# SMD_cree_driver_led-mosfet0023-GoldPhoen.net
KiCad netlist of a schematic drawn in EAGLE
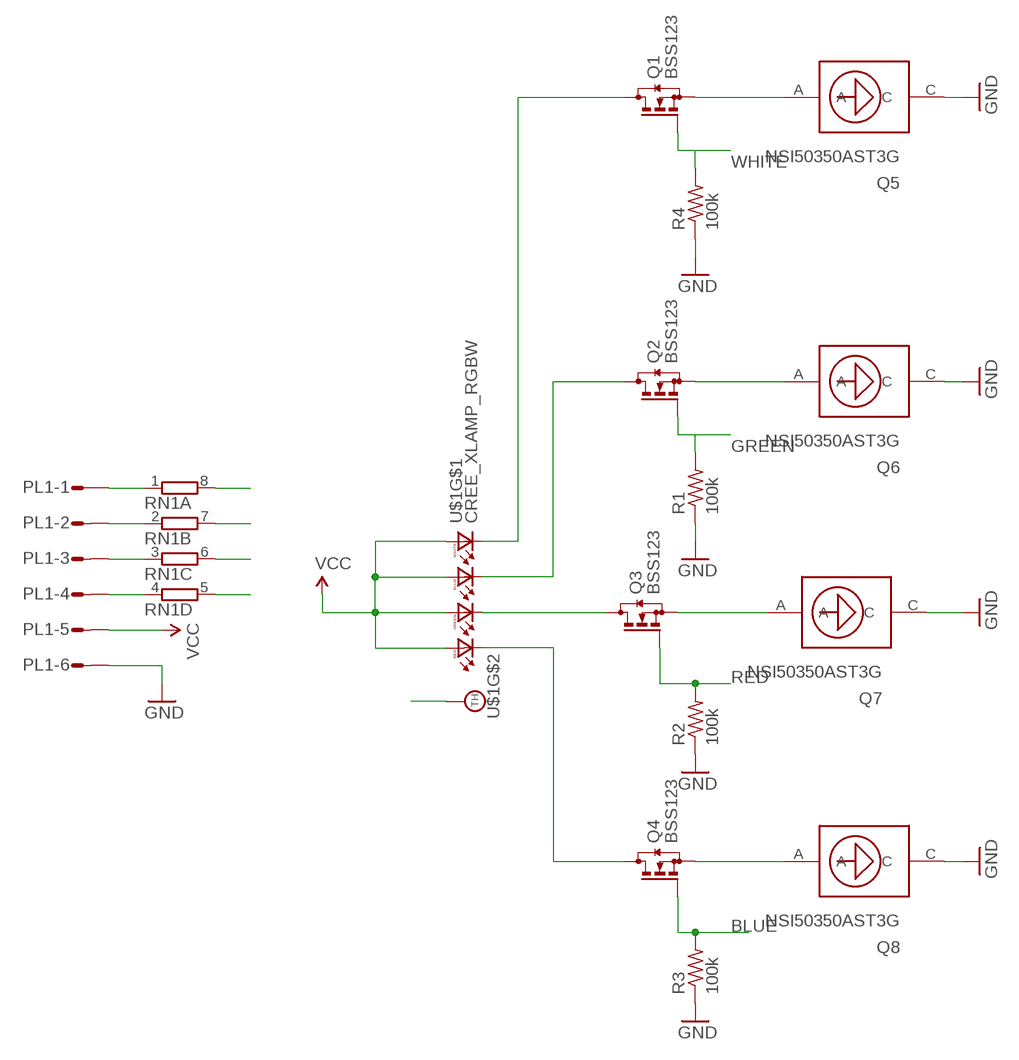
[diagram p0: schematic, sheet 1]

(export (version "E")
  (design (tool "Eeschema 10.0.6"))
  (components
    (comp (ref "PL1")
      (value "DF3-06R")
      (footprint "eagle-import:DF3R-06")
      (libsource (lib "eagle-import") (part "DF3-06R"))
    )
    (comp (ref "Q1")
      (value "BSS123")
      (footprint "eagle-import:SOT23")
      (libsource (lib "eagle-import") (part "BSS123"))
    )
    (comp (ref "Q2")
      (value "BSS123")
      (footprint "eagle-import:SOT23")
      (libsource (lib "eagle-import") (part "BSS123"))
    )
    (comp (ref "Q3")
      (value "BSS123")
      (footprint "eagle-import:SOT23")
      (libsource (lib "eagle-import") (part "BSS123"))
    )
    (comp (ref "Q4")
      (value "BSS123")
      (footprint "eagle-import:SOT23")
      (libsource (lib "eagle-import") (part "BSS123"))
    )
    (comp (ref "Q5")
      (value "NSI50350AST3G")
      (footprint "eagle-import:SMC-2")
      (libsource (lib "eagle-import") (part "NSI50350AST3G"))
    )
    (comp (ref "Q6")
      (value "NSI50350AST3G")
      (footprint "eagle-import:SMC-2")
      (libsource (lib "eagle-import") (part "NSI50350AST3G"))
    )
    (comp (ref "Q7")
      (value "NSI50350AST3G")
      (footprint "eagle-import:SMC-2")
      (libsource (lib "eagle-import") (part "NSI50350AST3G"))
    )
    (comp (ref "Q8")
      (value "NSI50350AST3G")
      (footprint "eagle-import:SMC-2")
      (libsource (lib "eagle-import") (part "NSI50350AST3G"))
    )
    (comp (ref "R1")
      (value "100k")
      (footprint "eagle-import:R0402")
      (libsource (lib "eagle-import") (part "R-US_R0402"))
    )
    (comp (ref "R2")
      (value "100k")
      (footprint "eagle-import:R0402")
      (libsource (lib "eagle-import") (part "R-US_R0402"))
    )
    (comp (ref "R3")
      (value "100k")
      (footprint "eagle-import:R0402")
      (libsource (lib "eagle-import") (part "R-US_R0402"))
    )
    (comp (ref "R4")
      (value "100k")
      (footprint "eagle-import:R0402")
      (libsource (lib "eagle-import") (part "R-US_R0402"))
    )
    (comp (ref "RN1")
      (value "4R-N0603-ARC")
      (footprint "eagle-import:0603-ARC")
      (libsource (lib "eagle-import") (part "4R-N0603-ARC"))
    )
    (comp (ref "U$1")
      (value "CREE_XLAMP_RGBW")
      (footprint "eagle-import:CREE_XLAMP_XML")
      (libsource (lib "eagle-import") (part "CREE_XLAMP_RGBW"))
    )
  )
  (nets
    (net (code "1") (name "/BLUE") (class "Default")
      (node (ref "Q4") (pin "1") (pinfunction "G_1") (pintype "passive"))
      (node (ref "R3") (pin "2") (pinfunction "2_2") (pintype "passive"))
      (node (ref "RN1") (pin "7") (pinfunction "2_7") (pintype "passive"))
    )
    (net (code "2") (name "/GREEN") (class "Default")
      (node (ref "Q2") (pin "1") (pinfunction "G_1") (pintype "passive"))
      (node (ref "R1") (pin "2") (pinfunction "2_2") (pintype "passive"))
      (node (ref "RN1") (pin "6") (pinfunction "2_6") (pintype "passive"))
    )
    (net (code "3") (name "/RED") (class "Default")
      (node (ref "Q3") (pin "1") (pinfunction "G_1") (pintype "passive"))
      (node (ref "R2") (pin "2") (pinfunction "2_2") (pintype "passive"))
      (node (ref "RN1") (pin "5") (pinfunction "2_5") (pintype "passive"))
    )
    (net (code "4") (name "/WHITE") (class "Default")
      (node (ref "Q1") (pin "1") (pinfunction "G_1") (pintype "passive"))
      (node (ref "R4") (pin "2") (pinfunction "2_2") (pintype "passive"))
      (node (ref "RN1") (pin "8") (pinfunction "2_8") (pintype "passive"))
    )
    (net (code "5") (name "GND") (class "Default")
      (node (ref "PL1") (pin "6") (pinfunction "S_6") (pintype "passive"))
      (node (ref "Q5") (pin "C") (pinfunction "C_C") (pintype "bidirectional"))
      (node (ref "Q6") (pin "C") (pinfunction "C_C") (pintype "bidirectional"))
      (node (ref "Q7") (pin "C") (pinfunction "C_C") (pintype "bidirectional"))
      (node (ref "Q8") (pin "C") (pinfunction "C_C") (pintype "bidirectional"))
      (node (ref "R1") (pin "1") (pinfunction "1_1") (pintype "passive"))
      (node (ref "R2") (pin "1") (pinfunction "1_1") (pintype "passive"))
      (node (ref "R3") (pin "1") (pinfunction "1_1") (pintype "passive"))
      (node (ref "R4") (pin "1") (pinfunction "1_1") (pintype "passive"))
    )
    (net (code "6") (name "Net-(PL1A-S)") (class "Default")
      (node (ref "PL1") (pin "1") (pinfunction "S_1") (pintype "passive"))
      (node (ref "RN1") (pin "1") (pinfunction "1_1") (pintype "passive"))
    )
    (net (code "7") (name "Net-(PL1B-S)") (class "Default")
      (node (ref "PL1") (pin "2") (pinfunction "S_2") (pintype "passive"))
      (node (ref "RN1") (pin "2") (pinfunction "1_2") (pintype "passive"))
    )
    (net (code "8") (name "Net-(PL1C-S)") (class "Default")
      (node (ref "PL1") (pin "3") (pinfunction "S_3") (pintype "passive"))
      (node (ref "RN1") (pin "3") (pinfunction "1_3") (pintype "passive"))
    )
    (net (code "9") (name "Net-(PL1D-S)") (class "Default")
      (node (ref "PL1") (pin "4") (pinfunction "S_4") (pintype "passive"))
      (node (ref "RN1") (pin "4") (pinfunction "1_4") (pintype "passive"))
    )
    (net (code "10") (name "Net-(Q1-D)") (class "Default")
      (node (ref "Q1") (pin "3") (pinfunction "D_3") (pintype "passive"))
      (node (ref "U$1") (pin "5") (pinfunction "WC_5") (pintype "passive"))
    )
    (net (code "11") (name "Net-(Q1-S)") (class "Default")
      (node (ref "Q1") (pin "2") (pinfunction "S_2") (pintype "passive"))
      (node (ref "Q5") (pin "A") (pinfunction "A_A") (pintype "bidirectional"))
    )
    (net (code "12") (name "Net-(Q2-D)") (class "Default")
      (node (ref "Q2") (pin "3") (pinfunction "D_3") (pintype "passive"))
      (node (ref "U$1") (pin "6") (pinfunction "BC_6") (pintype "passive"))
    )
    (net (code "13") (name "Net-(Q2-S)") (class "Default")
      (node (ref "Q2") (pin "2") (pinfunction "S_2") (pintype "passive"))
      (node (ref "Q6") (pin "A") (pinfunction "A_A") (pintype "bidirectional"))
    )
    (net (code "14") (name "Net-(Q3-D)") (class "Default")
      (node (ref "Q3") (pin "3") (pinfunction "D_3") (pintype "passive"))
      (node (ref "U$1") (pin "7") (pinfunction "GC_7") (pintype "passive"))
    )
    (net (code "15") (name "Net-(Q3-S)") (class "Default")
      (node (ref "Q3") (pin "2") (pinfunction "S_2") (pintype "passive"))
      (node (ref "Q7") (pin "A") (pinfunction "A_A") (pintype "bidirectional"))
    )
    (net (code "16") (name "Net-(Q4-D)") (class "Default")
      (node (ref "Q4") (pin "3") (pinfunction "D_3") (pintype "passive"))
      (node (ref "U$1") (pin "8") (pinfunction "RC_8") (pintype "passive"))
    )
    (net (code "17") (name "Net-(Q4-S)") (class "Default")
      (node (ref "Q4") (pin "2") (pinfunction "S_2") (pintype "passive"))
      (node (ref "Q8") (pin "A") (pinfunction "A_A") (pintype "bidirectional"))
    )
    (net (code "18") (name "VCC") (class "Default")
      (node (ref "PL1") (pin "5") (pinfunction "S_5") (pintype "passive"))
      (node (ref "U$1") (pin "1") (pinfunction "RA_1") (pintype "passive"))
      (node (ref "U$1") (pin "2") (pinfunction "GA_2") (pintype "passive"))
      (node (ref "U$1") (pin "3") (pinfunction "BA_3") (pintype "passive"))
      (node (ref "U$1") (pin "4") (pinfunction "WA_4") (pintype "passive"))
    )
    (net (code "19") (name "unconnected-(U$1B-TH-PadP$1)") (class "Default")
      (node (ref "U$1") (pin "P$1") (pinfunction "TH_P$1") (pintype "passive"))
    )
  )
)
